# tiny_function_generator_w_output_filter.net
KiCad netlist of a schematic drawn in EAGLE
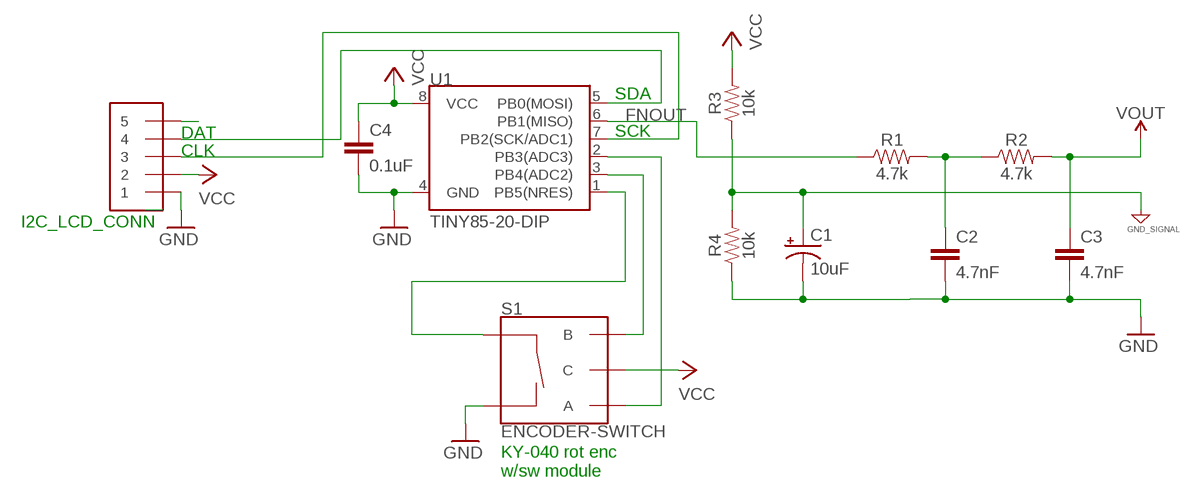
[diagram p0: schematic, sheet 1]

(export (version "E")
  (design (tool "Eeschema 10.0.6"))
  (components
    (comp (ref "C1")
      (value "10uF")
      (footprint "eagle-import:CPOL-RADIAL-2.5MM-5MM")
      (libsource (lib "eagle-import") (part "10UF-POLAR-RADIAL-2.5MM-25V-20%"))
    )
    (comp (ref "C2")
      (value "4.7nF")
      (footprint "eagle-import:0603")
      (libsource (lib "eagle-import") (part "4.7NF-50V-10%(0603)"))
    )
    (comp (ref "C3")
      (value "4.7nF")
      (footprint "eagle-import:0603")
      (libsource (lib "eagle-import") (part "4.7NF-50V-10%(0603)"))
    )
    (comp (ref "C4")
      (value "0.1uF")
      (footprint "eagle-import:CAP-PTH-SMALL-KIT")
      (libsource (lib "eagle-import") (part "0.1UF-KIT-EZ-50V-20%"))
    )
    (comp (ref "J1")
      (value "1X5")
      (footprint "eagle-import:3.5MM-5P")
      (libsource (lib "eagle-import") (part "1X5"))
    )
    (comp (ref "R1")
      (value "4.7k")
      (footprint "eagle-import:0603")
      (libsource (lib "eagle-import") (part "4.7KOHM-0603-1/10W-1%"))
    )
    (comp (ref "R2")
      (value "4.7k")
      (footprint "eagle-import:0603")
      (libsource (lib "eagle-import") (part "4.7KOHM-0603-1/10W-1%"))
    )
    (comp (ref "R3")
      (value "10k")
      (footprint "eagle-import:AXIAL-0.3")
      (libsource (lib "eagle-import") (part "10KOHM-HORIZ-1/6W-5%"))
    )
    (comp (ref "R4")
      (value "10k")
      (footprint "eagle-import:AXIAL-0.3")
      (libsource (lib "eagle-import") (part "10KOHM-HORIZ-1/6W-5%"))
    )
    (comp (ref "S1")
      (value "ENCODER-SWITCH")
      (footprint "eagle-import:ROTARY_ENC_PLAIN")
      (libsource (lib "eagle-import") (part "ENCODER-SWITCH"))
    )
    (comp (ref "U1")
      (value "TINY85-20-DIP")
      (footprint "eagle-import:DIP08_MCU")
      (libsource (lib "eagle-import") (part "ATTINY45TINY85-20-DIP"))
    )
  )
  (nets
    (net (code "1") (name "/FNOUT") (class "Default")
      (node (ref "R1") (pin "1") (pinfunction "1_1") (pintype "passive"))
      (node (ref "U1") (pin "6") (pinfunction "PB1(MISO)_6") (pintype "bidirectional"))
    )
    (net (code "2") (name "GND") (class "Default")
      (node (ref "C1") (pin "2") (pinfunction "-_2") (pintype "passive"))
      (node (ref "C2") (pin "2") (pinfunction "2_2") (pintype "passive"))
      (node (ref "C3") (pin "2") (pinfunction "2_2") (pintype "passive"))
      (node (ref "C4") (pin "2") (pinfunction "2_2") (pintype "passive"))
      (node (ref "J1") (pin "1") (pinfunction "1_1") (pintype "passive"))
      (node (ref "R4") (pin "P$1") (pinfunction "1_P$1") (pintype "passive"))
      (node (ref "S1") (pin "SW-") (pinfunction "SW-_SW-") (pintype "bidirectional"))
      (node (ref "U1") (pin "4") (pinfunction "GND_4") (pintype "bidirectional"))
    )
    (net (code "3") (name "GND_SIGNAL") (class "Default")
      (node (ref "C1") (pin "1") (pinfunction "+_1") (pintype "passive"))
      (node (ref "R3") (pin "P$1") (pinfunction "1_P$1") (pintype "passive"))
      (node (ref "R4") (pin "P$2") (pinfunction "2_P$2") (pintype "passive"))
    )
    (net (code "4") (name "Net-(C2-Pad1)") (class "Default")
      (node (ref "C2") (pin "1") (pinfunction "1_1") (pintype "passive"))
      (node (ref "R1") (pin "2") (pinfunction "2_2") (pintype "passive"))
      (node (ref "R2") (pin "1") (pinfunction "1_1") (pintype "passive"))
    )
    (net (code "5") (name "Net-(U1-PB0(MOSI))") (class "Default")
      (node (ref "J1") (pin "4") (pinfunction "4_4") (pintype "passive"))
      (node (ref "U1") (pin "5") (pinfunction "PB0(MOSI)_5") (pintype "bidirectional"))
    )
    (net (code "6") (name "Net-(U1-PB2(SCK{slash}ADC1))") (class "Default")
      (node (ref "J1") (pin "3") (pinfunction "3_3") (pintype "passive"))
      (node (ref "U1") (pin "7") (pinfunction "PB2(SCK/ADC1)_7") (pintype "bidirectional"))
    )
    (net (code "7") (name "Net-(U1-PB3(ADC3))") (class "Default")
      (node (ref "S1") (pin "A") (pinfunction "A_A") (pintype "bidirectional"))
      (node (ref "U1") (pin "2") (pinfunction "PB3(ADC3)_2") (pintype "bidirectional"))
    )
    (net (code "8") (name "Net-(U1-PB4(ADC2))") (class "Default")
      (node (ref "S1") (pin "B") (pinfunction "B_B") (pintype "bidirectional"))
      (node (ref "U1") (pin "3") (pinfunction "PB4(ADC2)_3") (pintype "bidirectional"))
    )
    (net (code "9") (name "Net-(U1-PB5(NRES))") (class "Default")
      (node (ref "S1") (pin "SW+") (pinfunction "SW+_SW+") (pintype "bidirectional"))
      (node (ref "U1") (pin "1") (pinfunction "PB5(NRES)_1") (pintype "bidirectional"))
    )
    (net (code "10") (name "VCC") (class "Default")
      (node (ref "C4") (pin "1") (pinfunction "1_1") (pintype "passive"))
      (node (ref "J1") (pin "2") (pinfunction "2_2") (pintype "passive"))
      (node (ref "R3") (pin "P$2") (pinfunction "2_P$2") (pintype "passive"))
      (node (ref "S1") (pin "C") (pinfunction "C_C") (pintype "bidirectional"))
      (node (ref "U1") (pin "8") (pinfunction "VCC_8") (pintype "bidirectional"))
    )
    (net (code "11") (name "VOUT") (class "Default")
      (node (ref "C3") (pin "1") (pinfunction "1_1") (pintype "passive"))
      (node (ref "R2") (pin "2") (pinfunction "2_2") (pintype "passive"))
    )
    (net (code "12") (name "unconnected-(J1-Pad5)") (class "Default")
      (node (ref "J1") (pin "5") (pinfunction "5_5") (pintype "passive"))
    )
  )
)
